# MotorController.net
KiCad netlist of a schematic drawn in EAGLE
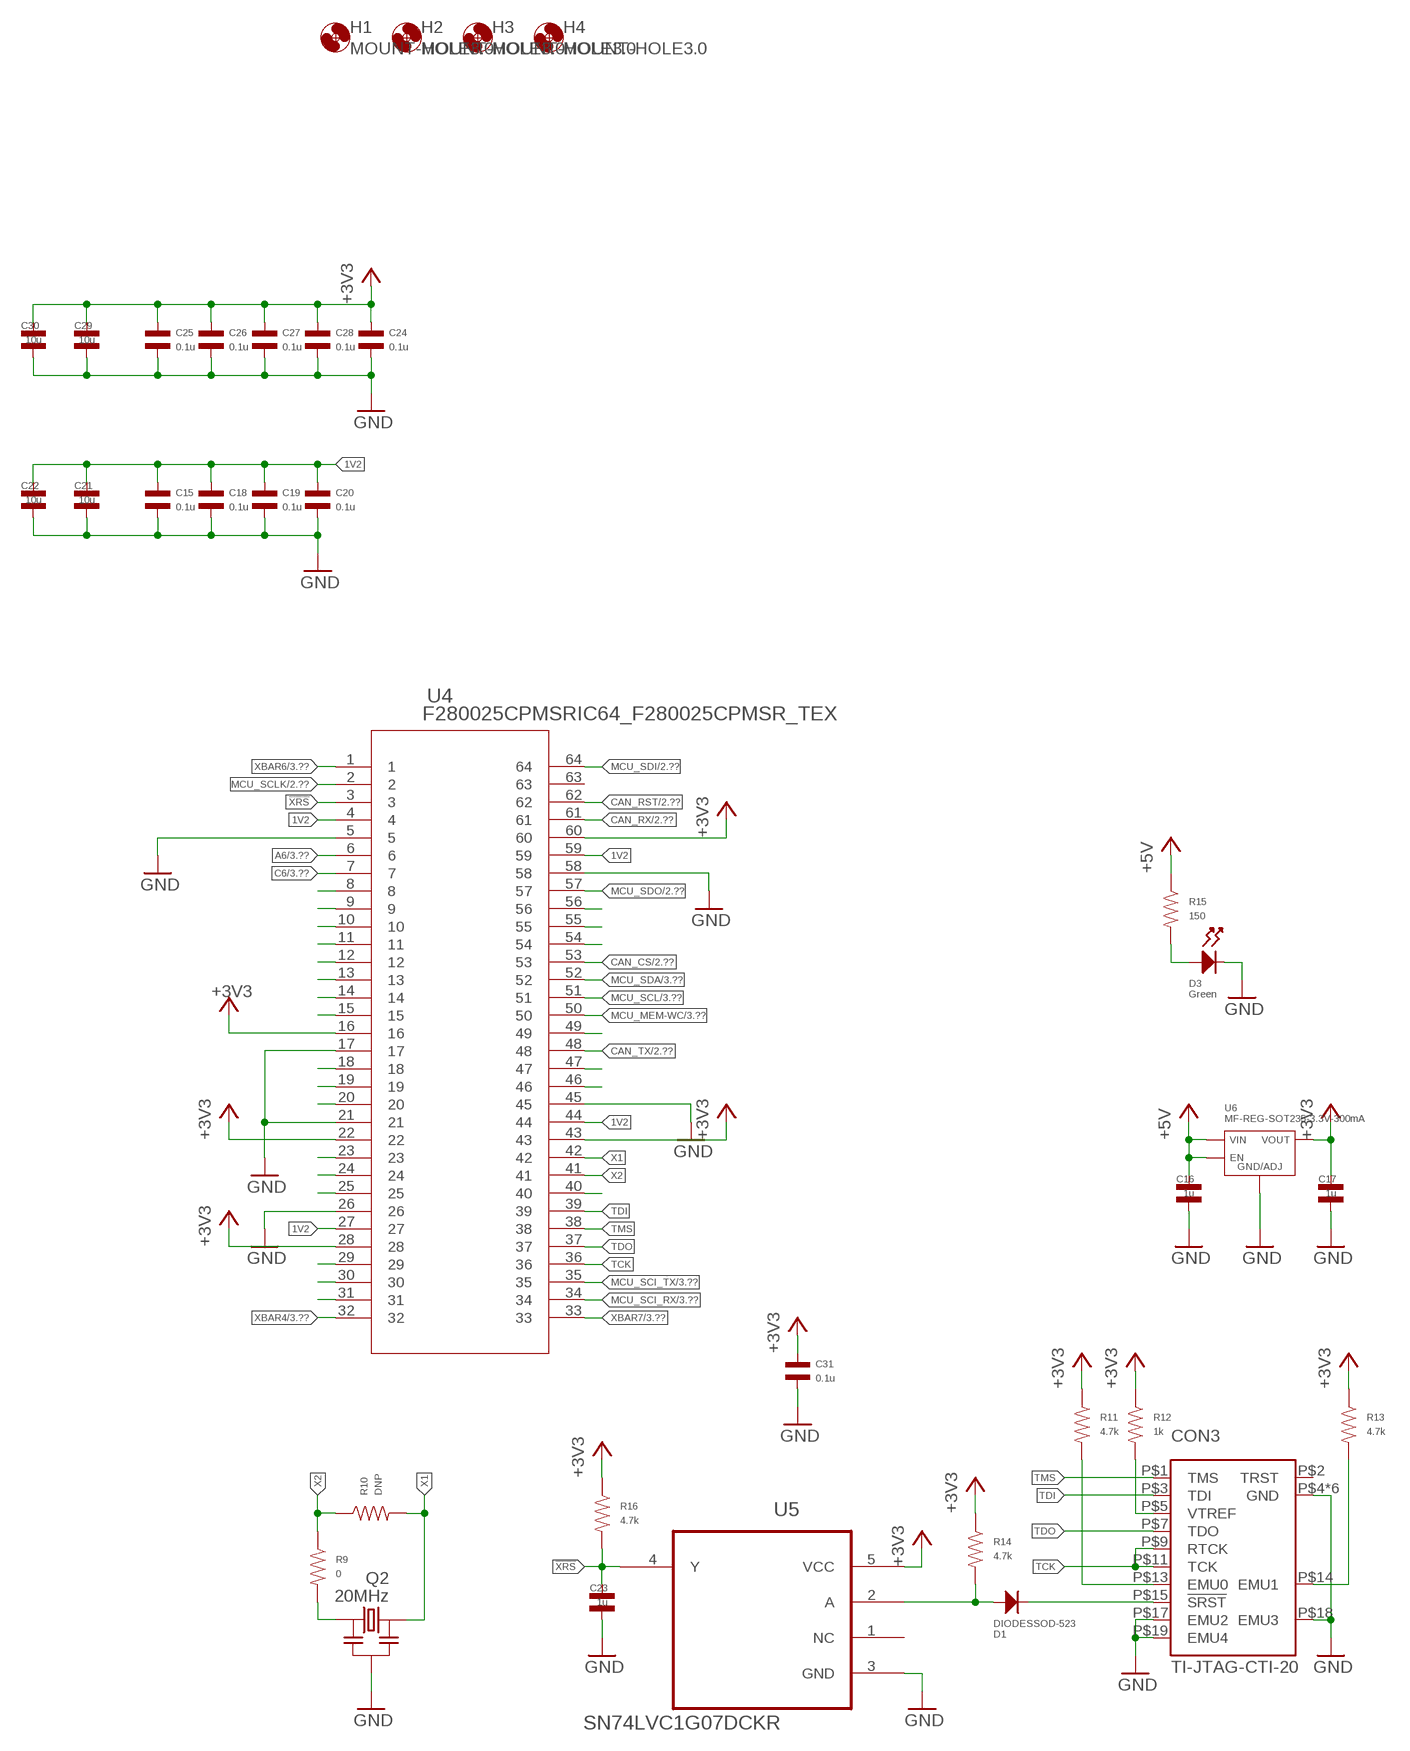
[diagram p0: schematic, sheet 1]
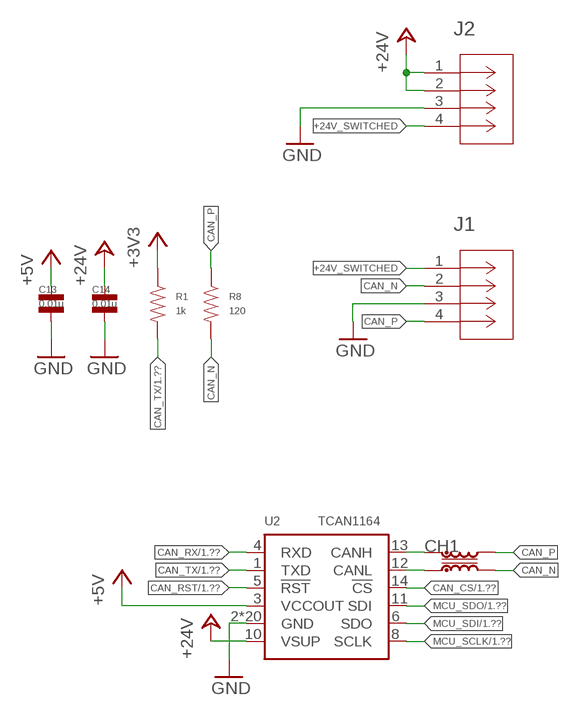
[diagram p1: schematic, sheet 2]
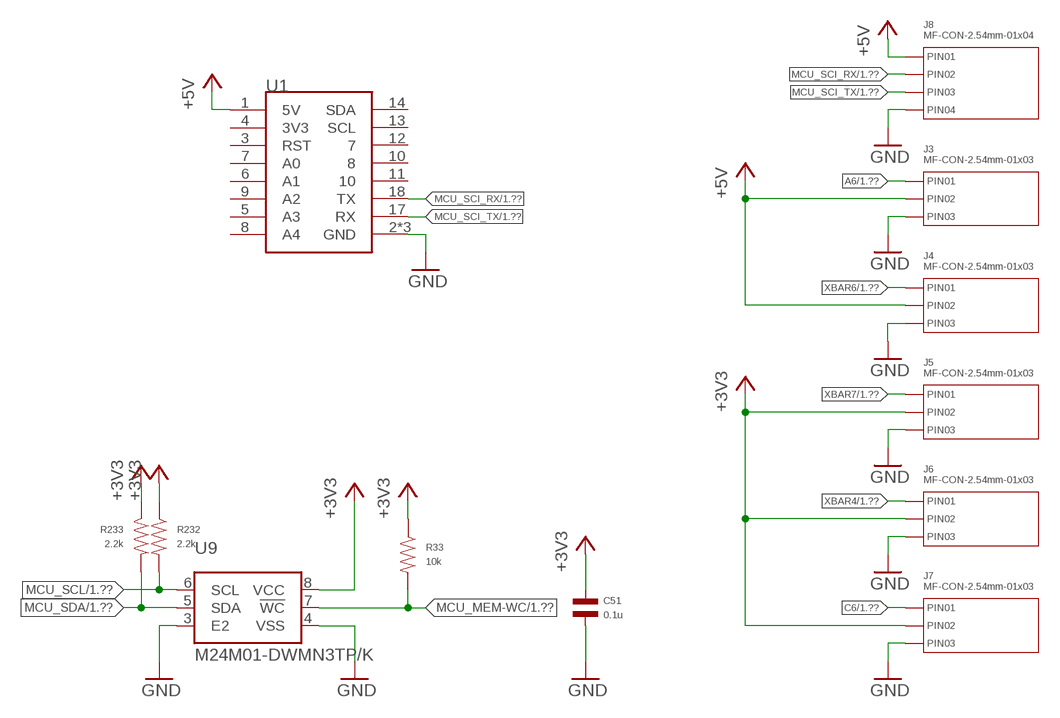
[diagram p2: schematic, sheet 3]

(export (version "E")
  (design (tool "Eeschema 10.0.6"))
  (components
    (comp (ref "C51")
      (value "0.1u")
      (footprint "eagle-import:C0402")
      (fields (field (name "MPN") "GCM155R71H104KE02D"))
      (libsource (lib "eagle-import") (part "MF_Passives_4704077_CAPACITOR_NP_0402"))
    )
    (comp (ref "J3")
      (value "MF-CON-2.54mm-01x03")
      (footprint "eagle-import:PTH_2.54MM_01X03")
      (fields (field (name "HOUSEPART") "YES"))
      (libsource (lib "eagle-import") (part "CON_01X03_PTH_2.54MM"))
    )
    (comp (ref "J4")
      (value "MF-CON-2.54mm-01x03")
      (footprint "eagle-import:PTH_2.54MM_01X03")
      (fields (field (name "HOUSEPART") "YES"))
      (libsource (lib "eagle-import") (part "CON_01X03_PTH_2.54MM"))
    )
    (comp (ref "J5")
      (value "MF-CON-2.54mm-01x03")
      (footprint "eagle-import:PTH_2.54MM_01X03")
      (fields (field (name "HOUSEPART") "YES"))
      (libsource (lib "eagle-import") (part "CON_01X03_PTH_2.54MM"))
    )
    (comp (ref "J6")
      (value "MF-CON-2.54mm-01x03")
      (footprint "eagle-import:PTH_2.54MM_01X03")
      (fields (field (name "HOUSEPART") "YES"))
      (libsource (lib "eagle-import") (part "CON_01X03_PTH_2.54MM"))
    )
    (comp (ref "J7")
      (value "MF-CON-2.54mm-01x03")
      (footprint "eagle-import:PTH_2.54MM_01X03")
      (fields (field (name "HOUSEPART") "YES"))
      (libsource (lib "eagle-import") (part "CON_01X03_PTH_2.54MM"))
    )
    (comp (ref "J8")
      (value "MF-CON-2.54mm-01x04")
      (footprint "eagle-import:PTH_2.54MM_01X04")
      (fields (field (name "HOUSEPART") "YES"))
      (libsource (lib "eagle-import") (part "CON_01X04_PTH_2.54MM"))
    )
    (comp (ref "R33")
      (value "10k")
      (footprint "eagle-import:R0402")
      (fields (field (name "MPN") "ERJ-2RKF1002X"))
      (libsource (lib "eagle-import") (part "MF_Passives_4704077_RESISTOR_0402"))
    )
    (comp (ref "R232")
      (value "2.2k")
      (footprint "eagle-import:R0402")
      (fields (field (name "MPN") "ERJ-2RKF2201X"))
      (libsource (lib "eagle-import") (part "MF_Passives_4704077_RESISTOR_0402"))
    )
    (comp (ref "R233")
      (value "2.2k")
      (footprint "eagle-import:R0402")
      (fields (field (name "MPN") "ERJ-2RKF2201X"))
      (libsource (lib "eagle-import") (part "MF_Passives_4704077_RESISTOR_0402"))
    )
    (comp (ref "U1")
      (value "ESP32-C3")
      (footprint "eagle-import:ESP32-C3")
      (libsource (lib "eagle-import") (part "ESP32-C3"))
    )
    (comp (ref "U9")
      (value "M24M01-DWMN3TP/K")
      (footprint "eagle-import:SOIC-8")
      (libsource (lib "eagle-import") (part "M24M02-DWMN3TP/K"))
    )
    (comp (ref "C15")
      (value "0.1u")
      (footprint "eagle-import:C0402")
      (fields (field (name "MPN") "GCM155R71H104KE02D"))
      (libsource (lib "eagle-import") (part "CAPACITOR_NP_0402"))
    )
    (comp (ref "C16")
      (value "1u")
      (footprint "eagle-import:C0805")
      (fields (field (name "MPN") "CL21B105KAFNNNE"))
      (libsource (lib "eagle-import") (part "CAPACITOR_NP_0805"))
    )
    (comp (ref "C17")
      (value "1u")
      (footprint "eagle-import:C0805")
      (fields (field (name "MPN") "CL21B105KAFNNNE"))
      (libsource (lib "eagle-import") (part "CAPACITOR_NP_0805"))
    )
    (comp (ref "C18")
      (value "0.1u")
      (footprint "eagle-import:C0402")
      (fields (field (name "MPN") "GCM155R71H104KE02D"))
      (libsource (lib "eagle-import") (part "CAPACITOR_NP_0402"))
    )
    (comp (ref "C19")
      (value "0.1u")
      (footprint "eagle-import:C0402")
      (fields (field (name "MPN") "GCM155R71H104KE02D"))
      (libsource (lib "eagle-import") (part "CAPACITOR_NP_0402"))
    )
    (comp (ref "C20")
      (value "0.1u")
      (footprint "eagle-import:C0402")
      (fields (field (name "MPN") "GCM155R71H104KE02D"))
      (libsource (lib "eagle-import") (part "CAPACITOR_NP_0402"))
    )
    (comp (ref "C21")
      (value "10u")
      (footprint "eagle-import:C0805")
      (fields (field (name "MPN") "CL21A106KAYNNNE"))
      (libsource (lib "eagle-import") (part "CAPACITOR_NP_0805"))
    )
    (comp (ref "C22")
      (value "10u")
      (footprint "eagle-import:C0805")
      (fields (field (name "MPN") "CL21A106KAYNNNE"))
      (libsource (lib "eagle-import") (part "CAPACITOR_NP_0805"))
    )
    (comp (ref "C23")
      (value "1u")
      (footprint "eagle-import:C0402")
      (fields (field (name "MPN") "CL05A105KA5NQNC"))
      (libsource (lib "eagle-import") (part "CAPACITOR_NP_0402"))
    )
    (comp (ref "C24")
      (value "0.1u")
      (footprint "eagle-import:C0402")
      (fields (field (name "MPN") "GCM155R71H104KE02D"))
      (libsource (lib "eagle-import") (part "CAPACITOR_NP_0402"))
    )
    (comp (ref "C25")
      (value "0.1u")
      (footprint "eagle-import:C0402")
      (fields (field (name "MPN") "GCM155R71H104KE02D"))
      (libsource (lib "eagle-import") (part "CAPACITOR_NP_0402"))
    )
    (comp (ref "C26")
      (value "0.1u")
      (footprint "eagle-import:C0402")
      (fields (field (name "MPN") "GCM155R71H104KE02D"))
      (libsource (lib "eagle-import") (part "CAPACITOR_NP_0402"))
    )
    (comp (ref "C27")
      (value "0.1u")
      (footprint "eagle-import:C0402")
      (fields (field (name "MPN") "GCM155R71H104KE02D"))
      (libsource (lib "eagle-import") (part "CAPACITOR_NP_0402"))
    )
    (comp (ref "C28")
      (value "0.1u")
      (footprint "eagle-import:C0402")
      (fields (field (name "MPN") "GCM155R71H104KE02D"))
      (libsource (lib "eagle-import") (part "CAPACITOR_NP_0402"))
    )
    (comp (ref "C29")
      (value "10u")
      (footprint "eagle-import:C0805")
      (fields (field (name "MPN") "CL21A106KAYNNNE"))
      (libsource (lib "eagle-import") (part "CAPACITOR_NP_0805"))
    )
    (comp (ref "C30")
      (value "10u")
      (footprint "eagle-import:C0805")
      (fields (field (name "MPN") "CL21A106KAYNNNE"))
      (libsource (lib "eagle-import") (part "CAPACITOR_NP_0805"))
    )
    (comp (ref "C31")
      (value "0.1u")
      (footprint "eagle-import:C0402")
      (fields (field (name "MPN") "GCM155R71H104KE02D"))
      (libsource (lib "eagle-import") (part "MF_Passives_4704077_CAPACITOR_NP_0402"))
    )
    (comp (ref "CON3")
      (value "TI-JTAG-CTI-20")
      (footprint "eagle-import:FTR-110-51-L-D-06")
      (fields (field (name "MPN") "FTR-110-51-L-D-06"))
      (libsource (lib "eagle-import") (part "TI-JTAG-CTI-20"))
    )
    (comp (ref "D1")
      (value "DIODESSOD-523")
      (footprint "eagle-import:SOD523")
      (fields (field (name "MPN") "RB510SM-40FHT2R"))
      (libsource (lib "eagle-import") (part "DIODESSOD-523"))
    )
    (comp (ref "D3")
      (value "Green")
      (footprint "eagle-import:LED0603")
      (fields (field (name "HOUSEPART") "NO") (field (name "MPN") "SML-E12P8WT86"))
      (libsource (lib "eagle-import") (part "LED_SINGLE-0603"))
    )
    (comp (ref "H1")
      (value "MOUNT-HOLE3.0")
      (footprint "eagle-import:3,0")
      (libsource (lib "eagle-import") (part "MOUNT-HOLE3.0"))
    )
    (comp (ref "H2")
      (value "MOUNT-HOLE3.0")
      (footprint "eagle-import:3,0")
      (libsource (lib "eagle-import") (part "MOUNT-HOLE3.0"))
    )
    (comp (ref "H3")
      (value "MOUNT-HOLE3.0")
      (footprint "eagle-import:3,0")
      (libsource (lib "eagle-import") (part "MOUNT-HOLE3.0"))
    )
    (comp (ref "H4")
      (value "MOUNT-HOLE3.0")
      (footprint "eagle-import:3,0")
      (libsource (lib "eagle-import") (part "MOUNT-HOLE3.0"))
    )
    (comp (ref "Q2")
      (value "20MHz")
      (footprint "eagle-import:CSTNE")
      (fields (field (name "MPN") "CSTNE20M0V53C000R0"))
      (libsource (lib "eagle-import") (part "RESONATORCSTNE"))
    )
    (comp (ref "R9")
      (value "0")
      (footprint "eagle-import:R0402")
      (fields (field (name "MPN") "ERJ-2GE0R00X"))
      (libsource (lib "eagle-import") (part "RESISTOR_0402"))
    )
    (comp (ref "R10")
      (value "DNP")
      (footprint "eagle-import:R0402")
      (libsource (lib "eagle-import") (part "RESISTOR_0402"))
    )
    (comp (ref "R11")
      (value "4.7k")
      (footprint "eagle-import:R0402")
      (fields (field (name "MPN") "ERJ-2RKF4701X"))
      (libsource (lib "eagle-import") (part "RESISTOR_0402"))
    )
    (comp (ref "R12")
      (value "1k")
      (footprint "eagle-import:R0402")
      (fields (field (name "MPN") "ERJ-2RKF1001X"))
      (libsource (lib "eagle-import") (part "RESISTOR_0402"))
    )
    (comp (ref "R13")
      (value "4.7k")
      (footprint "eagle-import:R0402")
      (fields (field (name "MPN") "ERJ-2RKF4701X"))
      (libsource (lib "eagle-import") (part "RESISTOR_0402"))
    )
    (comp (ref "R14")
      (value "4.7k")
      (footprint "eagle-import:R0402")
      (fields (field (name "MPN") "ERJ-2RKF4701X"))
      (libsource (lib "eagle-import") (part "RESISTOR_0402"))
    )
    (comp (ref "R15")
      (value "150")
      (footprint "eagle-import:R0805")
      (fields (field (name "MPN") "ERJ-6GEYJ151V"))
      (libsource (lib "eagle-import") (part "RESISTOR_0805"))
    )
    (comp (ref "R16")
      (value "4.7k")
      (footprint "eagle-import:R0402")
      (fields (field (name "MPN") "ERJ-2RKF4701X"))
      (libsource (lib "eagle-import") (part "RESISTOR_0402"))
    )
    (comp (ref "U4")
      (value "F280025CPMSRIC64_F280025CPMSR_TEX")
      (footprint "eagle-import:IC64_F280025CPMSR_TEX")
      (fields
        (field (name "MANUFACTURER_PART_NUMBER") "F280025CPMSR")
        (field (name "COPYRIGHT") "Copyright (C) 2024 Ultra Librarian. All rights reserved.")
      )
      (libsource (lib "eagle-import") (part "F280025CPMSRIC64_F280025CPMSR_TEX"))
    )
    (comp (ref "U5")
      (value "SN74LVC1G07DCKR")
      (footprint "eagle-import:SOT65P210X110-5N")
      (libsource (lib "eagle-import") (part "SN74LVC1G07DCKR"))
    )
    (comp (ref "U6")
      (value "MF-REG-SOT235-3.3V-300mA")
      (footprint "eagle-import:SOT-23-5")
      (fields (field (name "HOUSEPART") "YES") (field (name "MPN") "TLV70233PDBVR"))
      (libsource (lib "eagle-import") (part "TLV70233PDBVR"))
    )
    (comp (ref "C13")
      (value "0.01u")
      (footprint "eagle-import:C0402")
      (fields (field (name "MPN") "CL05B103KB5NNNC"))
      (libsource (lib "eagle-import") (part "CAPACITOR_NP_0402"))
    )
    (comp (ref "C14")
      (value "0.01u")
      (footprint "eagle-import:C0402")
      (fields (field (name "MPN") "CL05B103KB5NNNC"))
      (libsource (lib "eagle-import") (part "CAPACITOR_NP_0402"))
    )
    (comp (ref "CH1")
      (value "CHOKE-COMMON_MODECM1210-LAIRD")
      (footprint "eagle-import:CM1210-LAIRD")
      (fields (field (name "MPN") "CM1210B104R-1A"))
      (libsource (lib "eagle-import") (part "CHOKE-COMMON_MODECM1210-LAIRD"))
    )
    (comp (ref "J1")
      (value "768250004CON_768250004_MOL")
      (footprint "eagle-import:CON_768250004_MOL")
      (fields
        (field (name "MANUFACTURER_PART_NUMBER") "768250004")
        (field (name "MPN") "0768250004")
        (field (name "COPYRIGHT") "Copyright (C) 2024 Ultra Librarian. All rights reserved.")
      )
      (libsource (lib "eagle-import") (part "768250004CON_768250004_MOL"))
    )
    (comp (ref "J2")
      (value "768250004CON_768250004_MOL")
      (footprint "eagle-import:CON_768250004_MOL")
      (fields
        (field (name "MANUFACTURER_PART_NUMBER") "768250004")
        (field (name "MPN") "0768250004")
        (field (name "COPYRIGHT") "Copyright (C) 2024 Ultra Librarian. All rights reserved.")
      )
      (libsource (lib "eagle-import") (part "768250004CON_768250004_MOL"))
    )
    (comp (ref "R1")
      (value "1k")
      (footprint "eagle-import:R0402")
      (fields (field (name "MPN") "ERJ-2RKF1001X"))
      (libsource (lib "eagle-import") (part "RESISTOR_0402"))
    )
    (comp (ref "R8")
      (value "120")
      (footprint "eagle-import:R0402")
      (fields (field (name "MPN") "ERJ-2GEJ121X"))
      (libsource (lib "eagle-import") (part "RESISTOR_0402"))
    )
    (comp (ref "U2")
      (value "TCAN1164")
      (footprint "eagle-import:CONV_TPS63021DSJ")
      (fields (field (name "MPN") "TCAN1164DMTRQ1"))
      (libsource (lib "eagle-import") (part "TCAN1164"))
    )
  )
  (nets
    (net (code "1") (name "+3V3") (class "Default")
      (node (ref "C17") (pin "P$1") (pinfunction "P$1_P$1") (pintype "passive"))
      (node (ref "C24") (pin "P$1") (pinfunction "P$1_P$1") (pintype "passive"))
      (node (ref "C25") (pin "P$1") (pinfunction "P$1_P$1") (pintype "passive"))
      (node (ref "C26") (pin "P$1") (pinfunction "P$1_P$1") (pintype "passive"))
      (node (ref "C27") (pin "P$1") (pinfunction "P$1_P$1") (pintype "passive"))
      (node (ref "C28") (pin "P$1") (pinfunction "P$1_P$1") (pintype "passive"))
      (node (ref "C29") (pin "P$1") (pinfunction "P$1_P$1") (pintype "passive"))
      (node (ref "C30") (pin "P$1") (pinfunction "P$1_P$1") (pintype "passive"))
      (node (ref "C31") (pin "P$1") (pinfunction "P$1_P$1") (pintype "passive"))
      (node (ref "C51") (pin "P$1") (pinfunction "P$1_P$1") (pintype "passive"))
      (node (ref "J5") (pin "P$2") (pinfunction "PIN2_P$2") (pintype "bidirectional"))
      (node (ref "J6") (pin "P$2") (pinfunction "PIN2_P$2") (pintype "bidirectional"))
      (node (ref "J7") (pin "P$2") (pinfunction "PIN2_P$2") (pintype "bidirectional"))
      (node (ref "R1") (pin "P$1") (pinfunction "P$1_P$1") (pintype "passive"))
      (node (ref "R11") (pin "P$1") (pinfunction "P$1_P$1") (pintype "passive"))
      (node (ref "R12") (pin "P$1") (pinfunction "P$1_P$1") (pintype "passive"))
      (node (ref "R13") (pin "P$1") (pinfunction "P$1_P$1") (pintype "passive"))
      (node (ref "R14") (pin "P$1") (pinfunction "P$1_P$1") (pintype "passive"))
      (node (ref "R16") (pin "P$1") (pinfunction "P$1_P$1") (pintype "passive"))
      (node (ref "R232") (pin "P$1") (pinfunction "P$1_P$1") (pintype "passive"))
      (node (ref "R233") (pin "P$1") (pinfunction "P$1_P$1") (pintype "passive"))
      (node (ref "R33") (pin "P$1") (pinfunction "P$1_P$1") (pintype "passive"))
      (node (ref "U4") (pin "16") (pinfunction "16_16") (pintype "passive"))
      (node (ref "U4") (pin "22") (pinfunction "22_22") (pintype "passive"))
      (node (ref "U4") (pin "28") (pinfunction "28_28") (pintype "passive"))
      (node (ref "U4") (pin "43") (pinfunction "43_43") (pintype "passive"))
      (node (ref "U4") (pin "60") (pinfunction "60_60") (pintype "passive"))
      (node (ref "U5") (pin "5") (pinfunction "VCC_5") (pintype "power_in"))
      (node (ref "U6") (pin "P$5") (pinfunction "VOUT_P$5") (pintype "bidirectional"))
      (node (ref "U9") (pin "8") (pinfunction "VCC_8") (pintype "power_in"))
    )
    (net (code "2") (name "+5V") (class "Default")
      (node (ref "C13") (pin "P$1") (pinfunction "P$1_P$1") (pintype "passive"))
      (node (ref "C16") (pin "P$1") (pinfunction "P$1_P$1") (pintype "passive"))
      (node (ref "J3") (pin "P$2") (pinfunction "PIN2_P$2") (pintype "bidirectional"))
      (node (ref "J4") (pin "P$2") (pinfunction "PIN2_P$2") (pintype "bidirectional"))
      (node (ref "J8") (pin "P$1") (pinfunction "PIN1_P$1") (pintype "bidirectional"))
      (node (ref "R15") (pin "P$1") (pinfunction "P$1_P$1") (pintype "passive"))
      (node (ref "U1") (pin "1") (pinfunction "5V_1") (pintype "bidirectional"))
      (node (ref "U2") (pin "3") (pinfunction "VCCOUT_3") (pintype "bidirectional"))
      (node (ref "U6") (pin "P$1") (pinfunction "VIN_P$1") (pintype "bidirectional"))
      (node (ref "U6") (pin "P$3") (pinfunction "EN_P$3") (pintype "bidirectional"))
    )
    (net (code "3") (name "+24V") (class "Default")
      (node (ref "C14") (pin "P$1") (pinfunction "P$1_P$1") (pintype "passive"))
      (node (ref "J2") (pin "1") (pinfunction "1_1") (pintype "passive"))
      (node (ref "J2") (pin "2") (pinfunction "2_2") (pintype "passive"))
      (node (ref "U2") (pin "10") (pinfunction "VSUP_10") (pintype "bidirectional"))
    )
    (net (code "4") (name "+24V_SWITCHED") (class "Default")
      (node (ref "J1") (pin "1") (pinfunction "1_1") (pintype "passive"))
      (node (ref "J2") (pin "4") (pinfunction "4_4") (pintype "passive"))
    )
    (net (code "5") (name "1V2") (class "Default")
      (node (ref "C15") (pin "P$1") (pinfunction "P$1_P$1") (pintype "passive"))
      (node (ref "C18") (pin "P$1") (pinfunction "P$1_P$1") (pintype "passive"))
      (node (ref "C19") (pin "P$1") (pinfunction "P$1_P$1") (pintype "passive"))
      (node (ref "C20") (pin "P$1") (pinfunction "P$1_P$1") (pintype "passive"))
      (node (ref "C21") (pin "P$1") (pinfunction "P$1_P$1") (pintype "passive"))
      (node (ref "C22") (pin "P$1") (pinfunction "P$1_P$1") (pintype "passive"))
      (node (ref "U4") (pin "27") (pinfunction "27_27") (pintype "passive"))
      (node (ref "U4") (pin "4") (pinfunction "4_4") (pintype "passive"))
      (node (ref "U4") (pin "44") (pinfunction "44_44") (pintype "passive"))
      (node (ref "U4") (pin "59") (pinfunction "59_59") (pintype "passive"))
    )
    (net (code "6") (name "A6") (class "Default")
      (node (ref "J3") (pin "P$1") (pinfunction "PIN1_P$1") (pintype "bidirectional"))
      (node (ref "U4") (pin "6") (pinfunction "6_6") (pintype "passive"))
    )
    (net (code "7") (name "C6") (class "Default")
      (node (ref "J7") (pin "P$1") (pinfunction "PIN1_P$1") (pintype "bidirectional"))
      (node (ref "U4") (pin "7") (pinfunction "7_7") (pintype "passive"))
    )
    (net (code "8") (name "CAN_CS") (class "Default")
      (node (ref "U2") (pin "14") (pinfunction "~{CS}_14") (pintype "bidirectional"))
      (node (ref "U4") (pin "53") (pinfunction "53_53") (pintype "passive"))
    )
    (net (code "9") (name "CAN_N") (class "Default")
      (node (ref "CH1") (pin "P$3") (pinfunction "3_P$3") (pintype "bidirectional"))
      (node (ref "J1") (pin "2") (pinfunction "2_2") (pintype "passive"))
      (node (ref "R8") (pin "P$2") (pinfunction "P$2_P$2") (pintype "passive"))
    )
    (net (code "10") (name "CAN_P") (class "Default")
      (node (ref "CH1") (pin "P$2") (pinfunction "2_P$2") (pintype "bidirectional"))
      (node (ref "J1") (pin "4") (pinfunction "4_4") (pintype "passive"))
      (node (ref "R8") (pin "P$1") (pinfunction "P$1_P$1") (pintype "passive"))
    )
    (net (code "11") (name "CAN_RST") (class "Default")
      (node (ref "U2") (pin "5") (pinfunction "~{RST}_5") (pintype "bidirectional"))
      (node (ref "U4") (pin "62") (pinfunction "62_62") (pintype "passive"))
    )
    (net (code "12") (name "CAN_RX") (class "Default")
      (node (ref "U2") (pin "4") (pinfunction "RXD_4") (pintype "bidirectional"))
      (node (ref "U4") (pin "61") (pinfunction "61_61") (pintype "passive"))
    )
    (net (code "13") (name "CAN_TX") (class "Default")
      (node (ref "R1") (pin "P$2") (pinfunction "P$2_P$2") (pintype "passive"))
      (node (ref "U2") (pin "1") (pinfunction "TXD_1") (pintype "bidirectional"))
      (node (ref "U4") (pin "48") (pinfunction "48_48") (pintype "passive"))
    )
    (net (code "14") (name "GND") (class "Default")
      (node (ref "C13") (pin "P$2") (pinfunction "P$2_P$2") (pintype "passive"))
      (node (ref "C14") (pin "P$2") (pinfunction "P$2_P$2") (pintype "passive"))
      (node (ref "C15") (pin "P$2") (pinfunction "P$2_P$2") (pintype "passive"))
      (node (ref "C16") (pin "P$2") (pinfunction "P$2_P$2") (pintype "passive"))
      (node (ref "C17") (pin "P$2") (pinfunction "P$2_P$2") (pintype "passive"))
      (node (ref "C18") (pin "P$2") (pinfunction "P$2_P$2") (pintype "passive"))
      (node (ref "C19") (pin "P$2") (pinfunction "P$2_P$2") (pintype "passive"))
      (node (ref "C20") (pin "P$2") (pinfunction "P$2_P$2") (pintype "passive"))
      (node (ref "C21") (pin "P$2") (pinfunction "P$2_P$2") (pintype "passive"))
      (node (ref "C22") (pin "P$2") (pinfunction "P$2_P$2") (pintype "passive"))
      (node (ref "C23") (pin "P$2") (pinfunction "P$2_P$2") (pintype "passive"))
      (node (ref "C24") (pin "P$2") (pinfunction "P$2_P$2") (pintype "passive"))
      (node (ref "C25") (pin "P$2") (pinfunction "P$2_P$2") (pintype "passive"))
      (node (ref "C26") (pin "P$2") (pinfunction "P$2_P$2") (pintype "passive"))
      (node (ref "C27") (pin "P$2") (pinfunction "P$2_P$2") (pintype "passive"))
      (node (ref "C28") (pin "P$2") (pinfunction "P$2_P$2") (pintype "passive"))
      (node (ref "C29") (pin "P$2") (pinfunction "P$2_P$2") (pintype "passive"))
      (node (ref "C30") (pin "P$2") (pinfunction "P$2_P$2") (pintype "passive"))
      (node (ref "C31") (pin "P$2") (pinfunction "P$2_P$2") (pintype "passive"))
      (node (ref "C51") (pin "P$2") (pinfunction "P$2_P$2") (pintype "passive"))
      (node (ref "CON3") (pin "P$10") (pinfunction "GND_P$10") (pintype "bidirectional"))
      (node (ref "CON3") (pin "P$12") (pinfunction "GND_P$12") (pintype "bidirectional"))
      (node (ref "CON3") (pin "P$16") (pinfunction "GND_P$16") (pintype "bidirectional"))
      (node (ref "CON3") (pin "P$17") (pinfunction "EMU2_P$17") (pintype "bidirectional"))
      (node (ref "CON3") (pin "P$18") (pinfunction "EMU3_P$18") (pintype "bidirectional"))
      (node (ref "CON3") (pin "P$19") (pinfunction "EMU4_P$19") (pintype "bidirectional"))
      (node (ref "CON3") (pin "P$20") (pinfunction "GND_P$20") (pintype "bidirectional"))
      (node (ref "CON3") (pin "P$4") (pinfunction "GND_P$4") (pintype "bidirectional"))
      (node (ref "CON3") (pin "P$8") (pinfunction "GND_P$8") (pintype "bidirectional"))
      (node (ref "D3") (pin "CATHODE") (pinfunction "CATHODE_CATHODE") (pintype "power_in"))
      (node (ref "J1") (pin "3") (pinfunction "3_3") (pintype "passive"))
      (node (ref "J2") (pin "3") (pinfunction "3_3") (pintype "passive"))
      (node (ref "J3") (pin "P$3") (pinfunction "PIN3_P$3") (pintype "bidirectional"))
      (node (ref "J4") (pin "P$3") (pinfunction "PIN3_P$3") (pintype "bidirectional"))
      (node (ref "J5") (pin "P$3") (pinfunction "PIN3_P$3") (pintype "bidirectional"))
      (node (ref "J6") (pin "P$3") (pinfunction "PIN3_P$3") (pintype "bidirectional"))
      (node (ref "J7") (pin "P$3") (pinfunction "PIN3_P$3") (pintype "bidirectional"))
      (node (ref "J8") (pin "P$4") (pinfunction "PIN4_P$4") (pintype "bidirectional"))
      (node (ref "Q2") (pin "2") (pinfunction "GND_2") (pintype "passive"))
      (node (ref "U1") (pin "15") (pinfunction "GND_15") (pintype "bidirectional"))
      (node (ref "U1") (pin "16") (pinfunction "GND_16") (pintype "bidirectional"))
      (node (ref "U1") (pin "2") (pinfunction "GND_2") (pintype "bidirectional"))
      (node (ref "U2") (pin "15") (pinfunction "GND_15") (pintype "bidirectional"))
      (node (ref "U2") (pin "15_1") (pinfunction "GND_15_1") (pintype "bidirectional"))
      (node (ref "U2") (pin "15_10") (pinfunction "GND_15_10") (pintype "bidirectional"))
      (node (ref "U2") (pin "15_11") (pinfunction "GND_15_11") (pintype "bidirectional"))
      (node (ref "U2") (pin "15_12") (pinfunction "GND_15_12") (pintype "bidirectional"))
      (node (ref "U2") (pin "15_15") (pinfunction "GND_15_15") (pintype "bidirectional"))
      (node (ref "U2") (pin "15_16") (pinfunction "GND_15_16") (pintype "bidirectional"))
      (node (ref "U2") (pin "15_17") (pinfunction "GND_15_17") (pintype "bidirectional"))
      (node (ref "U2") (pin "15_2") (pinfunction "GND_15_2") (pintype "bidirectional"))
      (node (ref "U2") (pin "15_21") (pinfunction "GND_15_21") (pintype "bidirectional"))
      (node (ref "U2") (pin "15_22") (pinfunction "GND_15_22") (pintype "bidirectional"))
      (node (ref "U2") (pin "15_23") (pinfunction "GND_15_23") (pintype "bidirectional"))
      (node (ref "U2") (pin "15_3") (pinfunction "GND_15_3") (pintype "bidirectional"))
      (node (ref "U2") (pin "15_4") (pinfunction "GND_15_4") (pintype "bidirectional"))
      (node (ref "U2") (pin "15_5") (pinfunction "GND_15_5") (pintype "bidirectional"))
      (node (ref "U2") (pin "15_6") (pinfunction "GND_15_6") (pintype "bidirectional"))
      (node (ref "U2") (pin "15_7") (pinfunction "GND_15_7") (pintype "bidirectional"))
      (node (ref "U2") (pin "15_8") (pinfunction "GND_15_8") (pintype "bidirectional"))
      (node (ref "U2") (pin "15_9") (pinfunction "GND_15_9") (pintype "bidirectional"))
      (node (ref "U2") (pin "2") (pinfunction "GND_2") (pintype "bidirectional"))
      (node (ref "U4") (pin "17") (pinfunction "17_17") (pintype "passive"))
      (node (ref "U4") (pin "21") (pinfunction "21_21") (pintype "passive"))
      (node (ref "U4") (pin "26") (pinfunction "26_26") (pintype "passive"))
      (node (ref "U4") (pin "45") (pinfunction "45_45") (pintype "passive"))
      (node (ref "U4") (pin "5") (pinfunction "5_5") (pintype "passive"))
      (node (ref "U4") (pin "58") (pinfunction "58_58") (pintype "passive"))
      (node (ref "U5") (pin "3") (pinfunction "GND_3") (pintype "passive"))
      (node (ref "U6") (pin "P$2") (pinfunction "GND/ADJ_P$2") (pintype "bidirectional"))
      (node (ref "U9") (pin "3") (pinfunction "E2_3") (pintype "power_in"))
      (node (ref "U9") (pin "4") (pinfunction "VSS_4") (pintype "power_in"))
    )
    (net (code "15") (name "MCU_MEM-WC") (class "Default")
      (node (ref "R33") (pin "P$2") (pinfunction "P$2_P$2") (pintype "passive"))
      (node (ref "U4") (pin "50") (pinfunction "50_50") (pintype "passive"))
      (node (ref "U9") (pin "7") (pinfunction "~{WC}_7") (pintype "power_in"))
    )
    (net (code "16") (name "MCU_SCI_RX") (class "Default")
      (node (ref "J8") (pin "P$2") (pinfunction "PIN2_P$2") (pintype "bidirectional"))
      (node (ref "U1") (pin "18") (pinfunction "TX_18") (pintype "bidirectional"))
      (node (ref "U4") (pin "34") (pinfunction "34_34") (pintype "passive"))
    )
    (net (code "17") (name "MCU_SCI_TX") (class "Default")
      (node (ref "J8") (pin "P$3") (pinfunction "PIN3_P$3") (pintype "bidirectional"))
      (node (ref "U1") (pin "17") (pinfunction "RX_17") (pintype "bidirectional"))
      (node (ref "U4") (pin "35") (pinfunction "35_35") (pintype "passive"))
    )
    (net (code "18") (name "MCU_SCL") (class "Default")
      (node (ref "R232") (pin "P$2") (pinfunction "P$2_P$2") (pintype "passive"))
      (node (ref "U4") (pin "51") (pinfunction "51_51") (pintype "passive"))
      (node (ref "U9") (pin "6") (pinfunction "SCL_6") (pintype "power_in"))
    )
    (net (code "19") (name "MCU_SCLK") (class "Default")
      (node (ref "U2") (pin "8") (pinfunction "SCLK_8") (pintype "bidirectional"))
      (node (ref "U4") (pin "2") (pinfunction "2_2") (pintype "passive"))
    )
    (net (code "20") (name "MCU_SDA") (class "Default")
      (node (ref "R233") (pin "P$2") (pinfunction "P$2_P$2") (pintype "passive"))
      (node (ref "U4") (pin "52") (pinfunction "52_52") (pintype "passive"))
      (node (ref "U9") (pin "5") (pinfunction "SDA_5") (pintype "power_in"))
    )
    (net (code "21") (name "MCU_SDI") (class "Default")
      (node (ref "U2") (pin "6") (pinfunction "SDO_6") (pintype "bidirectional"))
      (node (ref "U4") (pin "64") (pinfunction "64_64") (pintype "passive"))
    )
    (net (code "22") (name "MCU_SDO") (class "Default")
      (node (ref "U2") (pin "11") (pinfunction "SDI_11") (pintype "bidirectional"))
      (node (ref "U4") (pin "57") (pinfunction "57_57") (pintype "passive"))
    )
    (net (code "23") (name "Net-(CH1-1)") (class "Default")
      (node (ref "CH1") (pin "P$1") (pinfunction "1_P$1") (pintype "bidirectional"))
      (node (ref "U2") (pin "13") (pinfunction "CANH_13") (pintype "bidirectional"))
    )
    (net (code "24") (name "Net-(CH1-4)") (class "Default")
      (node (ref "CH1") (pin "P$4") (pinfunction "4_P$4") (pintype "bidirectional"))
      (node (ref "U2") (pin "12") (pinfunction "CANL_12") (pintype "bidirectional"))
    )
    (net (code "25") (name "Net-(CON3-EMU0)") (class "Default")
      (node (ref "CON3") (pin "P$13") (pinfunction "EMU0_P$13") (pintype "bidirectional"))
      (node (ref "R11") (pin "P$2") (pinfunction "P$2_P$2") (pintype "passive"))
    )
    (net (code "26") (name "Net-(CON3-EMU1)") (class "Default")
      (node (ref "CON3") (pin "P$14") (pinfunction "EMU1_P$14") (pintype "bidirectional"))
      (node (ref "R13") (pin "P$2") (pinfunction "P$2_P$2") (pintype "passive"))
    )
    (net (code "27") (name "Net-(CON3-VTREF)") (class "Default")
      (node (ref "CON3") (pin "P$5") (pinfunction "VTREF_P$5") (pintype "bidirectional"))
      (node (ref "R12") (pin "P$2") (pinfunction "P$2_P$2") (pintype "passive"))
    )
    (net (code "28") (name "Net-(CON3-~{SRST})") (class "Default")
      (node (ref "CON3") (pin "P$15") (pinfunction "~{SRST}_P$15") (pintype "bidirectional"))
      (node (ref "D1") (pin "C") (pinfunction "CATHODE_C") (pintype "bidirectional"))
    )
    (net (code "29") (name "Net-(D1-ANODE)") (class "Default")
      (node (ref "D1") (pin "A") (pinfunction "ANODE_A") (pintype "bidirectional"))
      (node (ref "R14") (pin "P$2") (pinfunction "P$2_P$2") (pintype "passive"))
      (node (ref "U5") (pin "2") (pinfunction "A_2") (pintype "input"))
    )
    (net (code "30") (name "Net-(D3-PadANODE)") (class "Default")
      (node (ref "D3") (pin "ANODE") (pinfunction "ANODE_ANODE") (pintype "power_in"))
      (node (ref "R15") (pin "P$2") (pinfunction "P$2_P$2") (pintype "passive"))
    )
    (net (code "31") (name "Net-(Q2-XOUT)") (class "Default")
      (node (ref "Q2") (pin "3") (pinfunction "XOUT_3") (pintype "passive"))
      (node (ref "R9") (pin "P$2") (pinfunction "P$2_P$2") (pintype "passive"))
    )
    (net (code "32") (name "TCK") (class "Default")
      (node (ref "CON3") (pin "P$11") (pinfunction "TCK_P$11") (pintype "bidirectional"))
      (node (ref "CON3") (pin "P$9") (pinfunction "RTCK_P$9") (pintype "bidirectional"))
      (node (ref "U4") (pin "36") (pinfunction "36_36") (pintype "passive"))
    )
    (net (code "33") (name "TDI") (class "Default")
      (node (ref "CON3") (pin "P$3") (pinfunction "TDI_P$3") (pintype "bidirectional"))
      (node (ref "U4") (pin "39") (pinfunction "39_39") (pintype "passive"))
    )
    (net (code "34") (name "TDO") (class "Default")
      (node (ref "CON3") (pin "P$7") (pinfunction "TDO_P$7") (pintype "bidirectional"))
      (node (ref "U4") (pin "37") (pinfunction "37_37") (pintype "passive"))
    )
    (net (code "35") (name "TMS") (class "Default")
      (node (ref "CON3") (pin "P$1") (pinfunction "TMS_P$1") (pintype "bidirectional"))
      (node (ref "U4") (pin "38") (pinfunction "38_38") (pintype "passive"))
    )
    (net (code "36") (name "X1") (class "Default")
      (node (ref "Q2") (pin "1") (pinfunction "XIN_1") (pintype "passive"))
      (node (ref "R10") (pin "P$2") (pinfunction "P$2_P$2") (pintype "passive"))
      (node (ref "U4") (pin "42") (pinfunction "42_42") (pintype "passive"))
    )
    (net (code "37") (name "X2") (class "Default")
      (node (ref "R10") (pin "P$1") (pinfunction "P$1_P$1") (pintype "passive"))
      (node (ref "R9") (pin "P$1") (pinfunction "P$1_P$1") (pintype "passive"))
      (node (ref "U4") (pin "41") (pinfunction "41_41") (pintype "passive"))
    )
    (net (code "38") (name "XBAR4") (class "Default")
      (node (ref "J6") (pin "P$1") (pinfunction "PIN1_P$1") (pintype "bidirectional"))
      (node (ref "U4") (pin "32") (pinfunction "32_32") (pintype "passive"))
    )
    (net (code "39") (name "XBAR6") (class "Default")
      (node (ref "J4") (pin "P$1") (pinfunction "PIN1_P$1") (pintype "bidirectional"))
      (node (ref "U4") (pin "1") (pinfunction "1_1") (pintype "passive"))
    )
    (net (code "40") (name "XBAR7") (class "Default")
      (node (ref "J5") (pin "P$1") (pinfunction "PIN1_P$1") (pintype "bidirectional"))
      (node (ref "U4") (pin "33") (pinfunction "33_33") (pintype "passive"))
    )
    (net (code "41") (name "unconnected-(CON3-TRST-PadP$2)") (class "Default")
      (node (ref "CON3") (pin "P$2") (pinfunction "TRST_P$2") (pintype "bidirectional"))
    )
    (net (code "42") (name "unconnected-(U1-3V3-Pad4)") (class "Default")
      (node (ref "U1") (pin "4") (pinfunction "3V3_4") (pintype "bidirectional"))
    )
    (net (code "43") (name "unconnected-(U1-7-Pad12)") (class "Default")
      (node (ref "U1") (pin "12") (pinfunction "7_12") (pintype "bidirectional"))
    )
    (net (code "44") (name "unconnected-(U1-8-Pad10)") (class "Default")
      (node (ref "U1") (pin "10") (pinfunction "8_10") (pintype "bidirectional"))
    )
    (net (code "45") (name "unconnected-(U1-10-Pad11)") (class "Default")
      (node (ref "U1") (pin "11") (pinfunction "10_11") (pintype "bidirectional"))
    )
    (net (code "46") (name "unconnected-(U1-A0-Pad7)") (class "Default")
      (node (ref "U1") (pin "7") (pinfunction "A0_7") (pintype "bidirectional"))
    )
    (net (code "47") (name "unconnected-(U1-A1-Pad6)") (class "Default")
      (node (ref "U1") (pin "6") (pinfunction "A1_6") (pintype "bidirectional"))
    )
    (net (code "48") (name "unconnected-(U1-A2-Pad9)") (class "Default")
      (node (ref "U1") (pin "9") (pinfunction "A2_9") (pintype "bidirectional"))
    )
    (net (code "49") (name "unconnected-(U1-A3-Pad5)") (class "Default")
      (node (ref "U1") (pin "5") (pinfunction "A3_5") (pintype "bidirectional"))
    )
    (net (code "50") (name "unconnected-(U1-A4-Pad8)") (class "Default")
      (node (ref "U1") (pin "8") (pinfunction "A4_8") (pintype "bidirectional"))
    )
    (net (code "51") (name "unconnected-(U1-RST-Pad3)") (class "Default")
      (node (ref "U1") (pin "3") (pinfunction "RST_3") (pintype "bidirectional"))
    )
    (net (code "52") (name "unconnected-(U1-SCL-Pad13)") (class "Default")
      (node (ref "U1") (pin "13") (pinfunction "SCL_13") (pintype "bidirectional"))
    )
    (net (code "53") (name "unconnected-(U1-SDA-Pad14)") (class "Default")
      (node (ref "U1") (pin "14") (pinfunction "SDA_14") (pintype "bidirectional"))
    )
    (net (code "54") (name "unconnected-(U4-Pad8)") (class "Default")
      (node (ref "U4") (pin "8") (pinfunction "8_8") (pintype "passive"))
    )
    (net (code "55") (name "unconnected-(U4-Pad9)") (class "Default")
      (node (ref "U4") (pin "9") (pinfunction "9_9") (pintype "passive"))
    )
    (net (code "56") (name "unconnected-(U4-Pad10)") (class "Default")
      (node (ref "U4") (pin "10") (pinfunction "10_10") (pintype "passive"))
    )
    (net (code "57") (name "unconnected-(U4-Pad11)") (class "Default")
      (node (ref "U4") (pin "11") (pinfunction "11_11") (pintype "passive"))
    )
    (net (code "58") (name "unconnected-(U4-Pad12)") (class "Default")
      (node (ref "U4") (pin "12") (pinfunction "12_12") (pintype "passive"))
    )
    (net (code "59") (name "unconnected-(U4-Pad13)") (class "Default")
      (node (ref "U4") (pin "13") (pinfunction "13_13") (pintype "passive"))
    )
    (net (code "60") (name "unconnected-(U4-Pad14)") (class "Default")
      (node (ref "U4") (pin "14") (pinfunction "14_14") (pintype "passive"))
    )
    (net (code "61") (name "unconnected-(U4-Pad15)") (class "Default")
      (node (ref "U4") (pin "15") (pinfunction "15_15") (pintype "passive"))
    )
    (net (code "62") (name "unconnected-(U4-Pad18)") (class "Default")
      (node (ref "U4") (pin "18") (pinfunction "18_18") (pintype "passive"))
    )
    (net (code "63") (name "unconnected-(U4-Pad19)") (class "Default")
      (node (ref "U4") (pin "19") (pinfunction "19_19") (pintype "passive"))
    )
    (net (code "64") (name "unconnected-(U4-Pad20)") (class "Default")
      (node (ref "U4") (pin "20") (pinfunction "20_20") (pintype "passive"))
    )
    (net (code "65") (name "unconnected-(U4-Pad23)") (class "Default")
      (node (ref "U4") (pin "23") (pinfunction "23_23") (pintype "passive"))
    )
    (net (code "66") (name "unconnected-(U4-Pad24)") (class "Default")
      (node (ref "U4") (pin "24") (pinfunction "24_24") (pintype "passive"))
    )
    (net (code "67") (name "unconnected-(U4-Pad25)") (class "Default")
      (node (ref "U4") (pin "25") (pinfunction "25_25") (pintype "passive"))
    )
    (net (code "68") (name "unconnected-(U4-Pad29)") (class "Default")
      (node (ref "U4") (pin "29") (pinfunction "29_29") (pintype "passive"))
    )
    (net (code "69") (name "unconnected-(U4-Pad30)") (class "Default")
      (node (ref "U4") (pin "30") (pinfunction "30_30") (pintype "passive"))
    )
    (net (code "70") (name "unconnected-(U4-Pad31)") (class "Default")
      (node (ref "U4") (pin "31") (pinfunction "31_31") (pintype "passive"))
    )
    (net (code "71") (name "unconnected-(U4-Pad40)") (class "Default")
      (node (ref "U4") (pin "40") (pinfunction "40_40") (pintype "passive"))
    )
    (net (code "72") (name "unconnected-(U4-Pad46)") (class "Default")
      (node (ref "U4") (pin "46") (pinfunction "46_46") (pintype "passive"))
    )
    (net (code "73") (name "unconnected-(U4-Pad47)") (class "Default")
      (node (ref "U4") (pin "47") (pinfunction "47_47") (pintype "passive"))
    )
    (net (code "74") (name "unconnected-(U4-Pad49)") (class "Default")
      (node (ref "U4") (pin "49") (pinfunction "49_49") (pintype "passive"))
    )
    (net (code "75") (name "unconnected-(U4-Pad54)") (class "Default")
      (node (ref "U4") (pin "54") (pinfunction "54_54") (pintype "passive"))
    )
    (net (code "76") (name "unconnected-(U4-Pad55)") (class "Default")
      (node (ref "U4") (pin "55") (pinfunction "55_55") (pintype "passive"))
    )
    (net (code "77") (name "unconnected-(U4-Pad56)") (class "Default")
      (node (ref "U4") (pin "56") (pinfunction "56_56") (pintype "passive"))
    )
    (net (code "78") (name "unconnected-(U4-Pad63)") (class "Default")
      (node (ref "U4") (pin "63") (pinfunction "63_63") (pintype "passive"))
    )
    (net (code "79") (name "unconnected-(U5-NC-Pad1)") (class "Default")
      (node (ref "U5") (pin "1") (pinfunction "NC_1") (pintype "no_connect"))
    )
    (net (code "80") (name "~{XRS}") (class "Default")
      (node (ref "C23") (pin "P$1") (pinfunction "P$1_P$1") (pintype "passive"))
      (node (ref "R16") (pin "P$2") (pinfunction "P$2_P$2") (pintype "passive"))
      (node (ref "U4") (pin "3") (pinfunction "3_3") (pintype "passive"))
      (node (ref "U5") (pin "4") (pinfunction "Y_4") (pintype "output"))
    )
  )
)
